# Scope_Design.net
KiCad netlist of a schematic drawn in Altium Designer
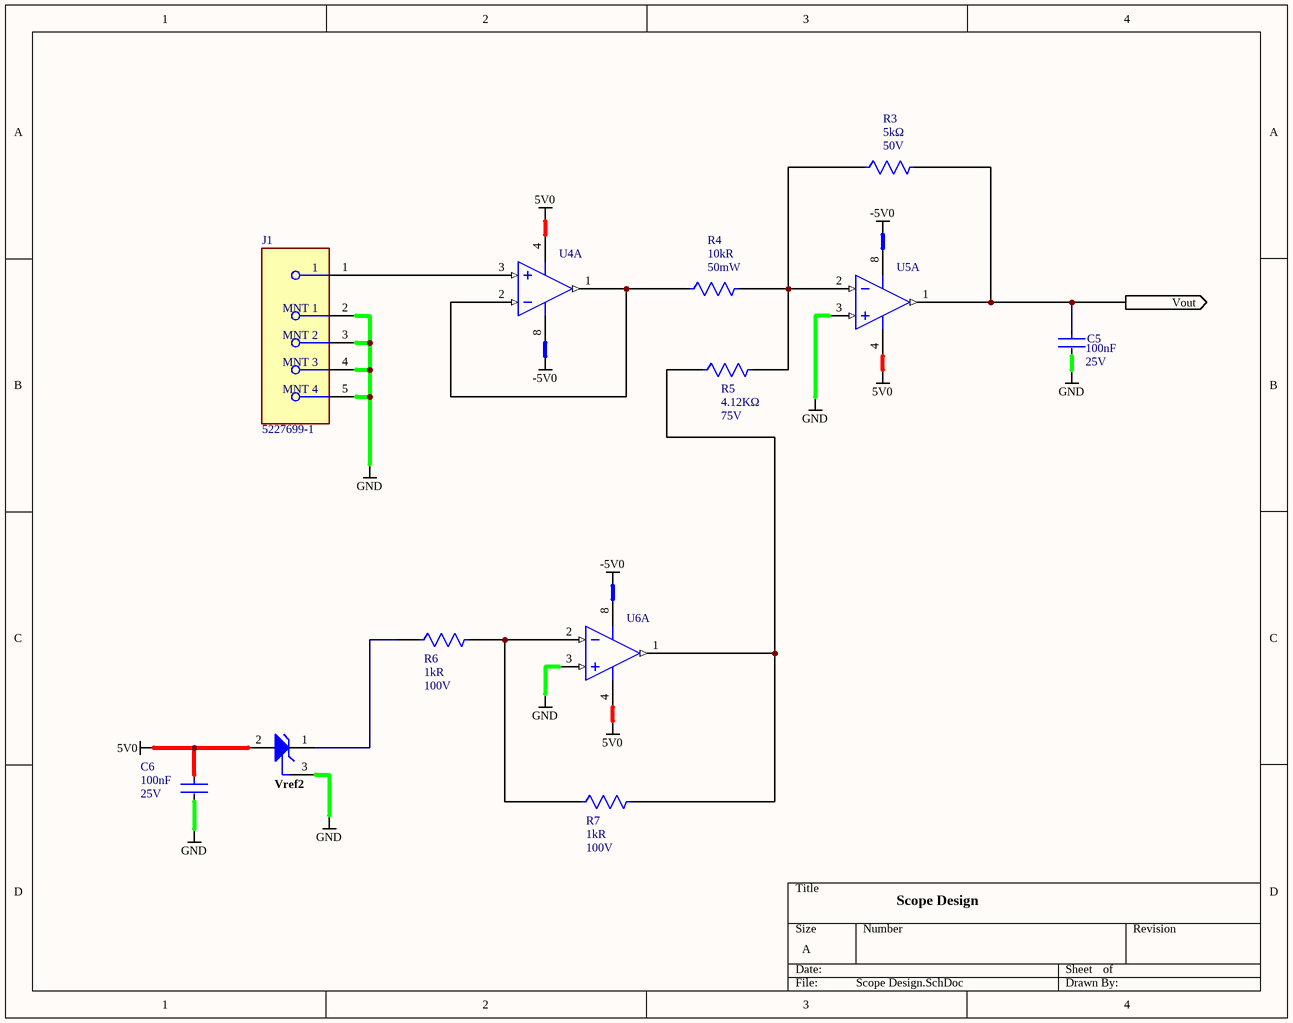
[diagram p0: Scope Design.SchDoc]

(export (version "E")
  (design (tool "Eeschema 10.0.6"))
  (components
    (comp (ref "C5")
      (value "0.1 uF")
      (footprint "FP-CL278-IPC_C")
      (description "Cap Ceramic 100nF 25V X5R ±10% SMD 0402 +85°C Paper T/R")
      (fields
        (field (name "VOLTAGE") "25V")
        (field (name "TOLERANCE") "10%")
        (field (name "CAPACITANCE") "100nF")
      )
      (libsource (lib "Altium Content Vault") (part "b4654b650e69147ec39a6b967a45e02"))
    )
    (comp (ref "C6")
      (value "0.1 uF")
      (footprint "FP-CL278-IPC_C")
      (description "Cap Ceramic 100nF 25V X5R ±10% SMD 0402 +85°C Paper T/R")
      (fields
        (field (name "VOLTAGE") "25V")
        (field (name "TOLERANCE") "10%")
        (field (name "CAPACITANCE") "100nF")
      )
      (libsource (lib "Altium Content Vault") (part "b4654b650e69147ec39a6b967a45e02"))
    )
    (comp (ref "J1")
      (value "5227699-1")
      (footprint "FP-5227699-1-MFG")
      (description "CONN BNC JACK STR 50 OHM PCB")
      (libsource (lib "Altium Content Vault") (part "c65b8a639cdaef1819ea20b5466f8fa"))
    )
    (comp (ref "R3")
      (value "RC0402FR-075KL")
      (footprint "FP-RC0402-MFG")
      (description "RES SMD 5K OHM 1% 1/16W 0402")
      (fields
        (field (name "RESISTANCE") "5kΩ")
        (field (name "MANUFACTURER") "Yageo")
        (field (name "VOLTAGE RATING") "50V")
        (field (name "TOLERANCE") "1%")
      )
      (libsource (lib "Altium Content Vault") (part "1029c3af85768c4190bb7ad29bc67b5"))
    )
    (comp (ref "R4")
      (value "RMCF0201FT10K0")
      (footprint "FP-RMCF0201-IPC_B")
      (description "RES 10K OHM 1% 1/20W 0201")
      (fields
        (field (name "MAX POWER DISSIPATION") "50mW")
        (field (name "RESISTANCE") "10kR")
        (field (name "TOLERANCE") "1%")
      )
      (libsource (lib "Altium Content Vault") (part "1029c3af85768c4190bb7ad29bc67b5"))
    )
    (comp (ref "R5")
      (value "4.12KΩ")
      (footprint "FP-RQ731J-IPC_C")
      (description "RQ73 0603 4.12KΩ  0.15W 10ppm/°C 0.1% 75V")
      (fields
        (field (name "OCTOPART") "https://octopart.com/rq73c1j4k12btd-te+connectivity-93908885")
        (field (name "TOLERANCE") "0.1%")
        (field (name "VOLTAGE RATING") "75V")
      )
      (libsource (lib "Altium Content Vault") (part "1029c3af85768c4190bb7ad29bc67b5"))
    )
    (comp (ref "R6")
      (value "RG2012P-102-B-T5")
      (footprint "FP-RG2012-IPC_B")
      (description "Automotive Metal Thin Film Chip Resistor, 0805, 1kΩ, 0.1%, 25ppm/°C, 0.125W, 150V")
      (fields
        (field (name "TOLERANCE") "0.1%")
        (field (name "RESISTANCE") "1kR")
        (field (name "VOLTAGE RATING") "100V")
      )
      (libsource (lib "Altium Content Vault") (part "1029c3af85768c4190bb7ad29bc67b5"))
    )
    (comp (ref "R7")
      (value "RG2012P-102-B-T5")
      (footprint "FP-RG2012-IPC_B")
      (description "Automotive Metal Thin Film Chip Resistor, 0805, 1kΩ, 0.1%, 25ppm/°C, 0.125W, 150V")
      (fields
        (field (name "TOLERANCE") "0.1%")
        (field (name "RESISTANCE") "1kR")
        (field (name "VOLTAGE RATING") "100V")
      )
      (libsource (lib "Altium Content Vault") (part "1029c3af85768c4190bb7ad29bc67b5"))
    )
    (comp (ref "U4")
      (value "OPA2330AIDGKR")
      (footprint "DGK0008A_M")
      (fields (field (name "MANUFACTURER") "Texas Instruments"))
      (libsource (lib "Altium Content Vault") (part "TI-OPA-8_2"))
    )
    (comp (ref "U5")
      (value "OPA2330AIDGKR")
      (footprint "DGK0008A_M")
      (fields (field (name "MANUFACTURER") "Texas Instruments"))
      (libsource (lib "Altium Content Vault") (part "TI-OPA-8_2"))
    )
    (comp (ref "U6")
      (value "OPA2330AIDGKR")
      (footprint "DGK0008A_M")
      (fields (field (name "MANUFACTURER") "Texas Instruments"))
      (libsource (lib "Altium Content Vault") (part "TI-OPA-8_2"))
    )
    (comp (ref "Vref2")
      (value "LM4040D20IDBZR")
      (footprint "DBZ0003A_N")
      (fields (field (name "MANUFACTURER") "Texas Instruments"))
      (libsource (lib "Altium Content Vault") (part "TI-LM4040D20DBZ3"))
    )
  )
  (nets
    (net (code "1") (name "-5V0") (class "Default")
      (node (ref "U4") (pin "8") (pinfunction "V+_8") (pintype "power_in"))
      (node (ref "U5") (pin "8") (pinfunction "V+_8") (pintype "power_in"))
      (node (ref "U6") (pin "8") (pinfunction "V+_8") (pintype "power_in"))
    )
    (net (code "2") (name "/Vout") (class "Default")
      (node (ref "C5") (pin "1") (pinfunction "1_1") (pintype "passive"))
      (node (ref "R3") (pin "2") (pinfunction "2_2") (pintype "passive"))
      (node (ref "U5") (pin "1") (pinfunction "OUT_A_1") (pintype "output"))
    )
    (net (code "3") (name "5V0") (class "Default")
      (node (ref "C6") (pin "1") (pinfunction "1_1") (pintype "passive"))
      (node (ref "U4") (pin "4") (pinfunction "V-_4") (pintype "power_in"))
      (node (ref "U5") (pin "4") (pinfunction "V-_4") (pintype "power_in"))
      (node (ref "U6") (pin "4") (pinfunction "V-_4") (pintype "power_in"))
      (node (ref "Vref2") (pin "2") (pinfunction "ANODE_2") (pintype "passive"))
    )
    (net (code "4") (name "GND") (class "Default")
      (node (ref "C5") (pin "2") (pinfunction "2_2") (pintype "passive"))
      (node (ref "C6") (pin "2") (pinfunction "2_2") (pintype "passive"))
      (node (ref "J1") (pin "2") (pinfunction "MNT_1_2") (pintype "passive"))
      (node (ref "J1") (pin "3") (pinfunction "MNT_2_3") (pintype "passive"))
      (node (ref "J1") (pin "4") (pinfunction "MNT_3_4") (pintype "passive"))
      (node (ref "J1") (pin "5") (pinfunction "MNT_4_5") (pintype "passive"))
      (node (ref "U5") (pin "3") (pinfunction "IN_A+_3") (pintype "input"))
      (node (ref "U6") (pin "3") (pinfunction "IN_A+_3") (pintype "input"))
      (node (ref "Vref2") (pin "3") (pinfunction "NC_3") (pintype "passive"))
    )
    (net (code "5") (name "Net-(U4A-IN_A+)") (class "Default")
      (node (ref "J1") (pin "1") (pinfunction "1_1") (pintype "passive"))
      (node (ref "U4") (pin "3") (pinfunction "IN_A+_3") (pintype "input"))
    )
    (net (code "6") (name "Net-(U4A-IN_A-)") (class "Default")
      (node (ref "R4") (pin "1") (pinfunction "1_1") (pintype "passive"))
      (node (ref "U4") (pin "1") (pinfunction "OUT_A_1") (pintype "output"))
      (node (ref "U4") (pin "2") (pinfunction "IN_A-_2") (pintype "input"))
    )
    (net (code "7") (name "Net-(U5A-IN_A-)") (class "Default")
      (node (ref "R3") (pin "1") (pinfunction "1_1") (pintype "passive"))
      (node (ref "R4") (pin "2") (pinfunction "2_2") (pintype "passive"))
      (node (ref "R5") (pin "2") (pinfunction "2_2") (pintype "passive"))
      (node (ref "U5") (pin "2") (pinfunction "IN_A-_2") (pintype "input"))
    )
    (net (code "8") (name "Net-(U6A-IN_A-)") (class "Default")
      (node (ref "R6") (pin "2") (pinfunction "2_2") (pintype "passive"))
      (node (ref "R7") (pin "1") (pinfunction "1_1") (pintype "passive"))
      (node (ref "U6") (pin "2") (pinfunction "IN_A-_2") (pintype "input"))
    )
    (net (code "9") (name "Net-(U6A-OUT_A)") (class "Default")
      (node (ref "R5") (pin "1") (pinfunction "1_1") (pintype "passive"))
      (node (ref "R7") (pin "2") (pinfunction "2_2") (pintype "passive"))
      (node (ref "U6") (pin "1") (pinfunction "OUT_A_1") (pintype "output"))
    )
    (net (code "10") (name "Net-(Vref2-CATHODE)") (class "Default")
      (node (ref "R6") (pin "1") (pinfunction "1_1") (pintype "passive"))
      (node (ref "Vref2") (pin "1") (pinfunction "CATHODE_1") (pintype "passive"))
    )
  )
)
